# MCPGrundplatte_16_Ausgabe.net
KiCad netlist of a schematic drawn in EAGLE
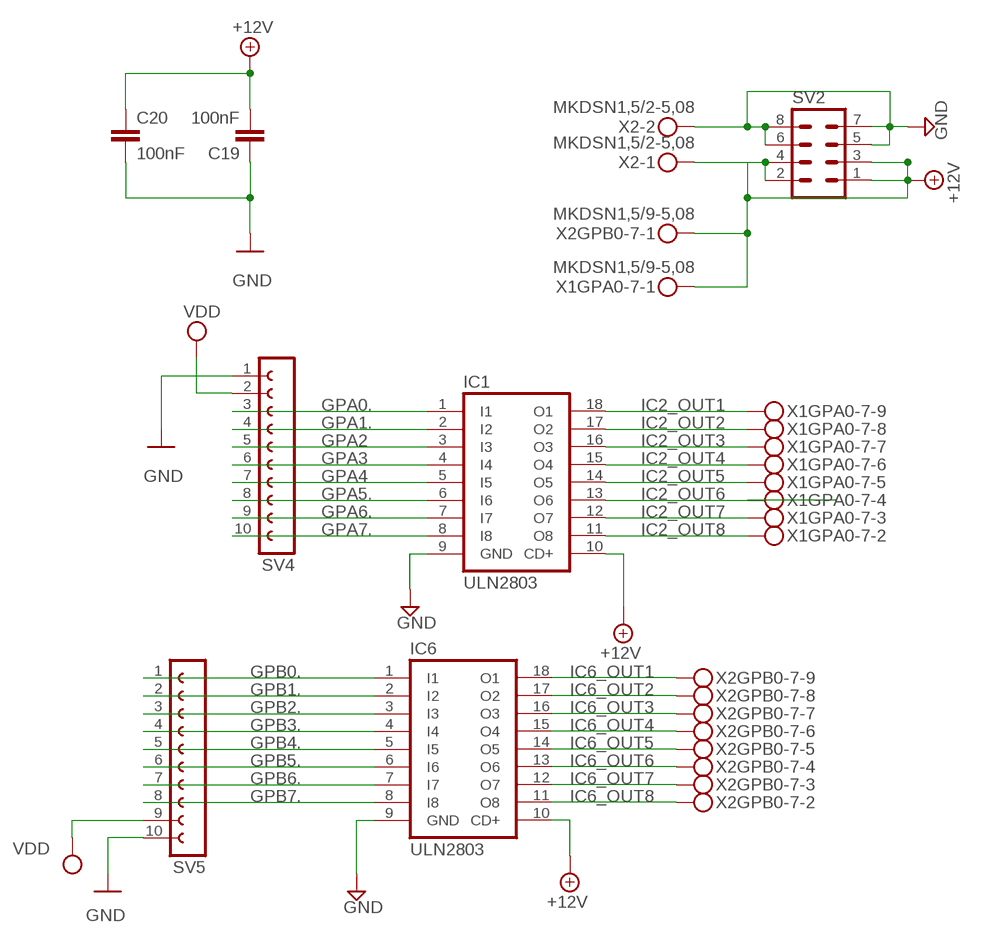
[diagram p0: schematic, sheet 1]

(export (version "E")
  (design (tool "Eeschema 10.0.6"))
  (components
    (comp (ref "C19")
      (value "100nF")
      (footprint "eagle-import:C025-024X044")
      (libsource (lib "eagle-import") (part "C-EU025-024X044"))
    )
    (comp (ref "C20")
      (value "100nF")
      (footprint "eagle-import:C025-024X044")
      (libsource (lib "eagle-import") (part "C-EU025-024X044"))
    )
    (comp (ref "IC1")
      (value "ULN2803")
      (footprint "eagle-import:DIL18")
      (libsource (lib "eagle-import") (part "ULN2803A"))
    )
    (comp (ref "IC6")
      (value "ULN2803")
      (footprint "eagle-import:DIL18")
      (libsource (lib "eagle-import") (part "ULN2803A"))
    )
    (comp (ref "SV2")
      (value "MA04-2")
      (footprint "eagle-import:MA04-2")
      (libsource (lib "eagle-import") (part "MA04-2"))
    )
    (comp (ref "SV4")
      (value "FE10-1")
      (footprint "eagle-import:FE10")
      (libsource (lib "eagle-import") (part "FE10-1"))
    )
    (comp (ref "SV5")
      (value "FE10-1")
      (footprint "eagle-import:FE10")
      (libsource (lib "eagle-import") (part "FE10-1"))
    )
    (comp (ref "X1GPA0-7")
      (value "MKDSN1,5/9-5,08")
      (footprint "eagle-import:MKDSN1,5_9-5,08")
      (libsource (lib "eagle-import") (part "MKDSN1,5/9-5,08"))
    )
    (comp (ref "X2")
      (value "MKDSN1,5/2-5,08")
      (footprint "eagle-import:MKDSN1,5_2-5,08")
      (libsource (lib "eagle-import") (part "MKDSN1,5/2-5,08"))
    )
    (comp (ref "X2GPB0-7")
      (value "MKDSN1,5/9-5,08")
      (footprint "eagle-import:MKDSN1,5_9-5,08")
      (libsource (lib "eagle-import") (part "MKDSN1,5/9-5,08"))
    )
  )
  (nets
    (net (code "1") (name "+12V") (class "Default")
      (node (ref "C19") (pin "2") (pinfunction "2_2") (pintype "passive"))
      (node (ref "C20") (pin "1") (pinfunction "1_1") (pintype "passive"))
      (node (ref "IC1") (pin "10") (pinfunction "CD+_10") (pintype "passive"))
      (node (ref "IC6") (pin "10") (pinfunction "CD+_10") (pintype "passive"))
      (node (ref "SV2") (pin "1") (pinfunction "1_1") (pintype "passive"))
      (node (ref "SV2") (pin "2") (pinfunction "2_2") (pintype "passive"))
      (node (ref "SV2") (pin "3") (pinfunction "3_3") (pintype "passive"))
      (node (ref "SV2") (pin "4") (pinfunction "4_4") (pintype "passive"))
      (node (ref "X1GPA0-7") (pin "1") (pinfunction "KL_1") (pintype "passive"))
      (node (ref "X2") (pin "1") (pinfunction "KL_1") (pintype "passive"))
      (node (ref "X2GPB0-7") (pin "1") (pinfunction "KL_1") (pintype "passive"))
    )
    (net (code "2") (name "/GPA0.") (class "Default")
      (node (ref "IC1") (pin "1") (pinfunction "I1_1") (pintype "input"))
      (node (ref "SV4") (pin "3") (pinfunction "3_3") (pintype "passive"))
    )
    (net (code "3") (name "/GPA1.") (class "Default")
      (node (ref "IC1") (pin "2") (pinfunction "I2_2") (pintype "input"))
      (node (ref "SV4") (pin "4") (pinfunction "4_4") (pintype "passive"))
    )
    (net (code "4") (name "/GPA2") (class "Default")
      (node (ref "IC1") (pin "3") (pinfunction "I3_3") (pintype "input"))
      (node (ref "SV4") (pin "5") (pinfunction "5_5") (pintype "passive"))
    )
    (net (code "5") (name "/GPA3") (class "Default")
      (node (ref "IC1") (pin "4") (pinfunction "I4_4") (pintype "input"))
      (node (ref "SV4") (pin "6") (pinfunction "6_6") (pintype "passive"))
    )
    (net (code "6") (name "/GPA4") (class "Default")
      (node (ref "IC1") (pin "5") (pinfunction "I5_5") (pintype "input"))
      (node (ref "SV4") (pin "7") (pinfunction "7_7") (pintype "passive"))
    )
    (net (code "7") (name "/GPA5.") (class "Default")
      (node (ref "IC1") (pin "6") (pinfunction "I6_6") (pintype "input"))
      (node (ref "SV4") (pin "8") (pinfunction "8_8") (pintype "passive"))
    )
    (net (code "8") (name "/GPA6.") (class "Default")
      (node (ref "IC1") (pin "7") (pinfunction "I7_7") (pintype "input"))
      (node (ref "SV4") (pin "9") (pinfunction "9_9") (pintype "passive"))
    )
    (net (code "9") (name "/GPA7.") (class "Default")
      (node (ref "IC1") (pin "8") (pinfunction "I8_8") (pintype "input"))
      (node (ref "SV4") (pin "10") (pinfunction "10_10") (pintype "passive"))
    )
    (net (code "10") (name "/GPB0.") (class "Default")
      (node (ref "IC6") (pin "1") (pinfunction "I1_1") (pintype "input"))
      (node (ref "SV5") (pin "1") (pinfunction "1_1") (pintype "passive"))
    )
    (net (code "11") (name "/GPB1.") (class "Default")
      (node (ref "IC6") (pin "2") (pinfunction "I2_2") (pintype "input"))
      (node (ref "SV5") (pin "2") (pinfunction "2_2") (pintype "passive"))
    )
    (net (code "12") (name "/GPB2.") (class "Default")
      (node (ref "IC6") (pin "3") (pinfunction "I3_3") (pintype "input"))
      (node (ref "SV5") (pin "3") (pinfunction "3_3") (pintype "passive"))
    )
    (net (code "13") (name "/GPB3.") (class "Default")
      (node (ref "IC6") (pin "4") (pinfunction "I4_4") (pintype "input"))
      (node (ref "SV5") (pin "4") (pinfunction "4_4") (pintype "passive"))
    )
    (net (code "14") (name "/GPB4.") (class "Default")
      (node (ref "IC6") (pin "5") (pinfunction "I5_5") (pintype "input"))
      (node (ref "SV5") (pin "5") (pinfunction "5_5") (pintype "passive"))
    )
    (net (code "15") (name "/GPB5.") (class "Default")
      (node (ref "IC6") (pin "6") (pinfunction "I6_6") (pintype "input"))
      (node (ref "SV5") (pin "6") (pinfunction "6_6") (pintype "passive"))
    )
    (net (code "16") (name "/GPB6.") (class "Default")
      (node (ref "IC6") (pin "7") (pinfunction "I7_7") (pintype "input"))
      (node (ref "SV5") (pin "7") (pinfunction "7_7") (pintype "passive"))
    )
    (net (code "17") (name "/GPB7.") (class "Default")
      (node (ref "IC6") (pin "8") (pinfunction "I8_8") (pintype "input"))
      (node (ref "SV5") (pin "8") (pinfunction "8_8") (pintype "passive"))
    )
    (net (code "18") (name "/IC2_OUT1") (class "Default")
      (node (ref "IC1") (pin "18") (pinfunction "O1_18") (pintype "open_collector"))
      (node (ref "X1GPA0-7") (pin "9") (pinfunction "KL_9") (pintype "passive"))
    )
    (net (code "19") (name "/IC2_OUT2") (class "Default")
      (node (ref "IC1") (pin "17") (pinfunction "O2_17") (pintype "open_collector"))
      (node (ref "X1GPA0-7") (pin "8") (pinfunction "KL_8") (pintype "passive"))
    )
    (net (code "20") (name "/IC2_OUT3") (class "Default")
      (node (ref "IC1") (pin "16") (pinfunction "O3_16") (pintype "open_collector"))
      (node (ref "X1GPA0-7") (pin "7") (pinfunction "KL_7") (pintype "passive"))
    )
    (net (code "21") (name "/IC2_OUT4") (class "Default")
      (node (ref "IC1") (pin "15") (pinfunction "O4_15") (pintype "open_collector"))
      (node (ref "X1GPA0-7") (pin "6") (pinfunction "KL_6") (pintype "passive"))
    )
    (net (code "22") (name "/IC2_OUT5") (class "Default")
      (node (ref "IC1") (pin "14") (pinfunction "O5_14") (pintype "open_collector"))
      (node (ref "X1GPA0-7") (pin "5") (pinfunction "KL_5") (pintype "passive"))
    )
    (net (code "23") (name "/IC2_OUT6") (class "Default")
      (node (ref "IC1") (pin "13") (pinfunction "O6_13") (pintype "open_collector"))
      (node (ref "X1GPA0-7") (pin "4") (pinfunction "KL_4") (pintype "passive"))
    )
    (net (code "24") (name "/IC2_OUT7") (class "Default")
      (node (ref "IC1") (pin "12") (pinfunction "O7_12") (pintype "open_collector"))
      (node (ref "X1GPA0-7") (pin "3") (pinfunction "KL_3") (pintype "passive"))
    )
    (net (code "25") (name "/IC2_OUT8") (class "Default")
      (node (ref "IC1") (pin "11") (pinfunction "O8_11") (pintype "open_collector"))
      (node (ref "X1GPA0-7") (pin "2") (pinfunction "KL_2") (pintype "passive"))
    )
    (net (code "26") (name "/IC6_OUT1") (class "Default")
      (node (ref "IC6") (pin "18") (pinfunction "O1_18") (pintype "open_collector"))
      (node (ref "X2GPB0-7") (pin "9") (pinfunction "KL_9") (pintype "passive"))
    )
    (net (code "27") (name "/IC6_OUT2") (class "Default")
      (node (ref "IC6") (pin "17") (pinfunction "O2_17") (pintype "open_collector"))
      (node (ref "X2GPB0-7") (pin "8") (pinfunction "KL_8") (pintype "passive"))
    )
    (net (code "28") (name "/IC6_OUT3") (class "Default")
      (node (ref "IC6") (pin "16") (pinfunction "O3_16") (pintype "open_collector"))
      (node (ref "X2GPB0-7") (pin "7") (pinfunction "KL_7") (pintype "passive"))
    )
    (net (code "29") (name "/IC6_OUT4") (class "Default")
      (node (ref "IC6") (pin "15") (pinfunction "O4_15") (pintype "open_collector"))
      (node (ref "X2GPB0-7") (pin "6") (pinfunction "KL_6") (pintype "passive"))
    )
    (net (code "30") (name "/IC6_OUT5") (class "Default")
      (node (ref "IC6") (pin "14") (pinfunction "O5_14") (pintype "open_collector"))
      (node (ref "X2GPB0-7") (pin "5") (pinfunction "KL_5") (pintype "passive"))
    )
    (net (code "31") (name "/IC6_OUT6") (class "Default")
      (node (ref "IC6") (pin "13") (pinfunction "O6_13") (pintype "open_collector"))
      (node (ref "X2GPB0-7") (pin "4") (pinfunction "KL_4") (pintype "passive"))
    )
    (net (code "32") (name "/IC6_OUT7") (class "Default")
      (node (ref "IC6") (pin "12") (pinfunction "O7_12") (pintype "open_collector"))
      (node (ref "X2GPB0-7") (pin "3") (pinfunction "KL_3") (pintype "passive"))
    )
    (net (code "33") (name "/IC6_OUT8") (class "Default")
      (node (ref "IC6") (pin "11") (pinfunction "O8_11") (pintype "open_collector"))
      (node (ref "X2GPB0-7") (pin "2") (pinfunction "KL_2") (pintype "passive"))
    )
    (net (code "34") (name "GND") (class "Default")
      (node (ref "C19") (pin "1") (pinfunction "1_1") (pintype "passive"))
      (node (ref "C20") (pin "2") (pinfunction "2_2") (pintype "passive"))
      (node (ref "IC1") (pin "9") (pinfunction "GND_9") (pintype "power_in"))
      (node (ref "IC6") (pin "9") (pinfunction "GND_9") (pintype "power_in"))
      (node (ref "SV2") (pin "5") (pinfunction "5_5") (pintype "passive"))
      (node (ref "SV2") (pin "6") (pinfunction "6_6") (pintype "passive"))
      (node (ref "SV2") (pin "7") (pinfunction "7_7") (pintype "passive"))
      (node (ref "SV2") (pin "8") (pinfunction "8_8") (pintype "passive"))
      (node (ref "SV4") (pin "1") (pinfunction "1_1") (pintype "passive"))
      (node (ref "SV5") (pin "10") (pinfunction "10_10") (pintype "passive"))
      (node (ref "X2") (pin "2") (pinfunction "KL_2") (pintype "passive"))
    )
    (net (code "35") (name "VDD") (class "Default")
      (node (ref "SV4") (pin "2") (pinfunction "2_2") (pintype "passive"))
      (node (ref "SV5") (pin "9") (pinfunction "9_9") (pintype "passive"))
    )
  )
)
